# SCH_UNLOCK.net
KiCad netlist of a schematic drawn in Altium Designer
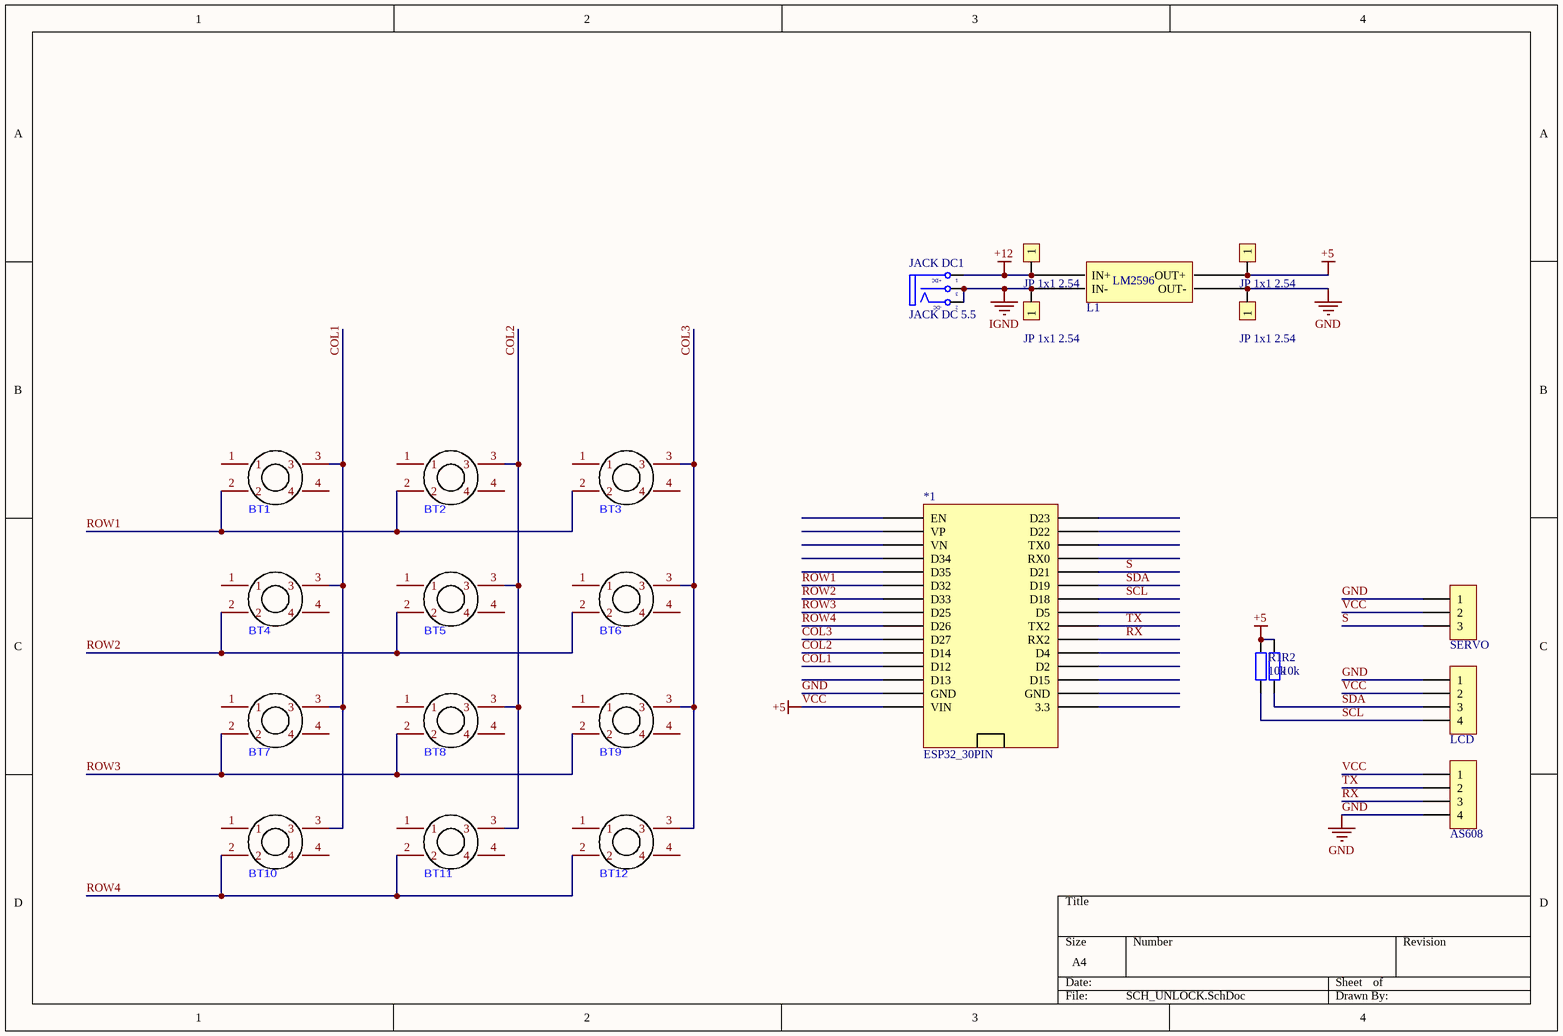
[diagram p0: SCH_UNLOCK.SchDoc]

(export (version "E")
  (design (tool "Eeschema 10.0.6"))
  (components
    (comp (ref "*1")
      (value "ESP32_30PIN")
      (footprint "ESP32_30PIN")
      (libsource (lib "myAltium") (part "ESP32_30PIN"))
    )
    (comp (ref "BT1")
      (value "Nut Nhan 4 chan 12x12")
      (footprint "12X12 BUTTOM Blue")
      (libsource (lib "Altium_Lib_by_KhueNguyenCreator") (part "Nut Nhan 4 chan 12x12"))
    )
    (comp (ref "BT2")
      (value "Nut Nhan 4 chan 12x12")
      (footprint "12X12 BUTTOM Blue")
      (libsource (lib "Altium_Lib_by_KhueNguyenCreator") (part "Nut Nhan 4 chan 12x12"))
    )
    (comp (ref "BT3")
      (value "Nut Nhan 4 chan 12x12")
      (footprint "12X12 BUTTOM Blue")
      (libsource (lib "Altium_Lib_by_KhueNguyenCreator") (part "Nut Nhan 4 chan 12x12"))
    )
    (comp (ref "BT4")
      (value "Nut Nhan 4 chan 12x12")
      (footprint "12X12 BUTTOM Blue")
      (libsource (lib "Altium_Lib_by_KhueNguyenCreator") (part "Nut Nhan 4 chan 12x12"))
    )
    (comp (ref "BT5")
      (value "Nut Nhan 4 chan 12x12")
      (footprint "12X12 BUTTOM Blue")
      (libsource (lib "Altium_Lib_by_KhueNguyenCreator") (part "Nut Nhan 4 chan 12x12"))
    )
    (comp (ref "BT6")
      (value "Nut Nhan 4 chan 12x12")
      (footprint "12X12 BUTTOM Blue")
      (libsource (lib "Altium_Lib_by_KhueNguyenCreator") (part "Nut Nhan 4 chan 12x12"))
    )
    (comp (ref "BT7")
      (value "Nut Nhan 4 chan 12x12")
      (footprint "12X12 BUTTOM Blue")
      (libsource (lib "Altium_Lib_by_KhueNguyenCreator") (part "Nut Nhan 4 chan 12x12"))
    )
    (comp (ref "BT8")
      (value "Nut Nhan 4 chan 12x12")
      (footprint "12X12 BUTTOM Blue")
      (libsource (lib "Altium_Lib_by_KhueNguyenCreator") (part "Nut Nhan 4 chan 12x12"))
    )
    (comp (ref "BT9")
      (value "Nut Nhan 4 chan 12x12")
      (footprint "12X12 BUTTOM Blue")
      (libsource (lib "Altium_Lib_by_KhueNguyenCreator") (part "Nut Nhan 4 chan 12x12"))
    )
    (comp (ref "BT10")
      (value "Nut Nhan 4 chan 12x12")
      (footprint "12X12 BUTTOM Blue")
      (libsource (lib "Altium_Lib_by_KhueNguyenCreator") (part "Nut Nhan 4 chan 12x12"))
    )
    (comp (ref "BT11")
      (value "Nut Nhan 4 chan 12x12")
      (footprint "12X12 BUTTOM Blue")
      (libsource (lib "Altium_Lib_by_KhueNguyenCreator") (part "Nut Nhan 4 chan 12x12"))
    )
    (comp (ref "BT12")
      (value "Nut Nhan 4 chan 12x12")
      (footprint "12X12 BUTTOM Blue")
      (libsource (lib "Altium_Lib_by_KhueNguyenCreator") (part "Nut Nhan 4 chan 12x12"))
    )
    (comp (ref "H1")
      (value "SERVO")
      (footprint "XH2.54M-3")
      (description "Cắm")
      (libsource (lib "Altium_Lib_by_KhueNguyenCreator") (part "Header 3P 2.54 Duc Thang"))
    )
    (comp (ref "H2")
      (value "LCD")
      (footprint "XH2.54M-4")
      (description "Cắm")
      (libsource (lib "Altium_Lib_by_KhueNguyenCreator") (part "Header 4P 2.54 Duc Thang"))
    )
    (comp (ref "H3")
      (value "AS608")
      (footprint "XH2.54M-4")
      (description "Cắm")
      (libsource (lib "Altium_Lib_by_KhueNguyenCreator") (part "Header 4P 2.54 Duc Thang"))
    )
    (comp (ref "JACK DC1")
      (value "JACK DC 5.5")
      (footprint "JACK DC 5.5")
      (libsource (lib "Altium_Lib_by_KhueNguyenCreator") (part "JACK DC 5.5"))
    )
    (comp (ref "JP1")
      (value "JP 1x1 2.54")
      (footprint "JP 1x1 DT")
      (description "Cắm")
      (libsource (lib "") (part "JP 1x1 2.54 Duc Cong_1"))
    )
    (comp (ref "JP2")
      (value "JP 1x1 2.54")
      (footprint "JP 1x1 DT")
      (description "Cắm")
      (libsource (lib "") (part "JP 1x1 2.54 Duc Cong_1"))
    )
    (comp (ref "JP3")
      (value "JP 1x1 2.54")
      (footprint "JP 1x1 DT")
      (description "Cắm")
      (libsource (lib "Altium_Lib_by_KhueNguyenCreator") (part "JP 1x1 2.54 Duc Cong"))
    )
    (comp (ref "JP4")
      (value "JP 1x1 2.54")
      (footprint "JP 1x1 DT")
      (description "Cắm")
      (libsource (lib "Altium_Lib_by_KhueNguyenCreator") (part "JP 1x1 2.54 Duc Cong"))
    )
    (comp (ref "L1")
      (value "BUCK_LM2596")
      (footprint "BUCK_LM2596")
      (libsource (lib "BUCK_LM2596_Library") (part "BUCK_LM2596"))
    )
    (comp (ref "R1")
      (value "10k")
      (footprint "tro vach 1/4w")
      (description "Căm")
      (libsource (lib "Altium_Lib_by_KhueNguyenCreator") (part "Tro Vach 1/4W 5% 10k"))
    )
    (comp (ref "R2")
      (value "10k")
      (footprint "tro vach 1/4w")
      (description "Căm")
      (libsource (lib "Altium_Lib_by_KhueNguyenCreator") (part "Tro Vach 1/4W 5% 10k"))
    )
  )
  (nets
    (net (code "1") (name "+5") (class "Default")
      (node (ref "*1") (pin "VIN") (pinfunction "VIN_VIN") (pintype "passive"))
      (node (ref "H1") (pin "2") (pinfunction "2_2") (pintype "passive"))
      (node (ref "H2") (pin "2") (pinfunction "2_2") (pintype "passive"))
      (node (ref "H3") (pin "1") (pinfunction "1_1") (pintype "passive"))
      (node (ref "JP2") (pin "1") (pinfunction "1_1") (pintype "passive"))
      (node (ref "L1") (pin "4") (pinfunction "OUT+_4") (pintype "passive"))
      (node (ref "R1") (pin "1") (pinfunction "1_1") (pintype "passive"))
      (node (ref "R2") (pin "1") (pinfunction "1_1") (pintype "passive"))
    )
    (net (code "2") (name "+12") (class "Default")
      (node (ref "JACK DC1") (pin "1") (pinfunction "T_1") (pintype "passive"))
      (node (ref "JP1") (pin "1") (pinfunction "1_1") (pintype "passive"))
      (node (ref "L1") (pin "1") (pinfunction "IN+_1") (pintype "passive"))
    )
    (net (code "3") (name "/COL1") (class "Default")
      (node (ref "*1") (pin "D12") (pinfunction "D12_D12") (pintype "passive"))
      (node (ref "BT1") (pin "3") (pinfunction "3_3") (pintype "passive"))
      (node (ref "BT10") (pin "3") (pinfunction "3_3") (pintype "passive"))
      (node (ref "BT4") (pin "3") (pinfunction "3_3") (pintype "passive"))
      (node (ref "BT7") (pin "3") (pinfunction "3_3") (pintype "passive"))
    )
    (net (code "4") (name "/COL2") (class "Default")
      (node (ref "*1") (pin "D14") (pinfunction "D14_D14") (pintype "passive"))
      (node (ref "BT11") (pin "3") (pinfunction "3_3") (pintype "passive"))
      (node (ref "BT2") (pin "3") (pinfunction "3_3") (pintype "passive"))
      (node (ref "BT5") (pin "3") (pinfunction "3_3") (pintype "passive"))
      (node (ref "BT8") (pin "3") (pinfunction "3_3") (pintype "passive"))
    )
    (net (code "5") (name "/COL3") (class "Default")
      (node (ref "*1") (pin "D27") (pinfunction "D27_D27") (pintype "passive"))
      (node (ref "BT12") (pin "3") (pinfunction "3_3") (pintype "passive"))
      (node (ref "BT3") (pin "3") (pinfunction "3_3") (pintype "passive"))
      (node (ref "BT6") (pin "3") (pinfunction "3_3") (pintype "passive"))
      (node (ref "BT9") (pin "3") (pinfunction "3_3") (pintype "passive"))
    )
    (net (code "6") (name "/ROW1") (class "Default")
      (node (ref "*1") (pin "D32") (pinfunction "D32_D32") (pintype "passive"))
      (node (ref "BT1") (pin "2") (pinfunction "2_2") (pintype "passive"))
      (node (ref "BT2") (pin "2") (pinfunction "2_2") (pintype "passive"))
      (node (ref "BT3") (pin "2") (pinfunction "2_2") (pintype "passive"))
    )
    (net (code "7") (name "/ROW2") (class "Default")
      (node (ref "*1") (pin "D33") (pinfunction "D33_D33") (pintype "passive"))
      (node (ref "BT4") (pin "2") (pinfunction "2_2") (pintype "passive"))
      (node (ref "BT5") (pin "2") (pinfunction "2_2") (pintype "passive"))
      (node (ref "BT6") (pin "2") (pinfunction "2_2") (pintype "passive"))
    )
    (net (code "8") (name "/ROW3") (class "Default")
      (node (ref "*1") (pin "D25") (pinfunction "D25_D25") (pintype "passive"))
      (node (ref "BT7") (pin "2") (pinfunction "2_2") (pintype "passive"))
      (node (ref "BT8") (pin "2") (pinfunction "2_2") (pintype "passive"))
      (node (ref "BT9") (pin "2") (pinfunction "2_2") (pintype "passive"))
    )
    (net (code "9") (name "/ROW4") (class "Default")
      (node (ref "*1") (pin "D26") (pinfunction "D26_D26") (pintype "passive"))
      (node (ref "BT10") (pin "2") (pinfunction "2_2") (pintype "passive"))
      (node (ref "BT11") (pin "2") (pinfunction "2_2") (pintype "passive"))
      (node (ref "BT12") (pin "2") (pinfunction "2_2") (pintype "passive"))
    )
    (net (code "10") (name "/RX") (class "Default")
      (node (ref "*1") (pin "RX2") (pinfunction "RX2_RX2") (pintype "passive"))
      (node (ref "H3") (pin "3") (pinfunction "3_3") (pintype "passive"))
    )
    (net (code "11") (name "/S") (class "Default")
      (node (ref "*1") (pin "D21") (pinfunction "D21_D21") (pintype "passive"))
      (node (ref "H1") (pin "3") (pinfunction "3_3") (pintype "passive"))
    )
    (net (code "12") (name "/SCL") (class "Default")
      (node (ref "*1") (pin "D18") (pinfunction "D18_D18") (pintype "passive"))
      (node (ref "H2") (pin "4") (pinfunction "4_4") (pintype "passive"))
      (node (ref "R1") (pin "2") (pinfunction "2_2") (pintype "passive"))
    )
    (net (code "13") (name "/SDA") (class "Default")
      (node (ref "*1") (pin "D19") (pinfunction "D19_D19") (pintype "passive"))
      (node (ref "H2") (pin "3") (pinfunction "3_3") (pintype "passive"))
      (node (ref "R2") (pin "2") (pinfunction "2_2") (pintype "passive"))
    )
    (net (code "14") (name "/TX") (class "Default")
      (node (ref "*1") (pin "TX2") (pinfunction "TX2_TX2") (pintype "passive"))
      (node (ref "H3") (pin "2") (pinfunction "2_2") (pintype "passive"))
    )
    (net (code "15") (name "GND") (class "Default")
      (node (ref "*1") (pin "GND") (pinfunction "GND_GND") (pintype "passive"))
      (node (ref "H1") (pin "1") (pinfunction "1_1") (pintype "passive"))
      (node (ref "H2") (pin "1") (pinfunction "1_1") (pintype "passive"))
      (node (ref "H3") (pin "4") (pinfunction "4_4") (pintype "passive"))
      (node (ref "JP4") (pin "1") (pinfunction "1_1") (pintype "passive"))
      (node (ref "L1") (pin "3") (pinfunction "OUT-_3") (pintype "passive"))
    )
    (net (code "16") (name "IGND") (class "Default")
      (node (ref "JACK DC1") (pin "2") (pinfunction "TN_2") (pintype "passive"))
      (node (ref "JACK DC1") (pin "3") (pinfunction "S_3") (pintype "power_in"))
      (node (ref "JP3") (pin "1") (pinfunction "1_1") (pintype "passive"))
      (node (ref "L1") (pin "2") (pinfunction "IN-_2") (pintype "passive"))
    )
    (net (code "17") (name "unconnected-(*1-Pad3.3)") (class "Default")
      (node (ref "*1") (pin "3.3") (pinfunction "3.3_3.3") (pintype "passive"))
    )
    (net (code "18") (name "unconnected-(*1-PadD2)") (class "Default")
      (node (ref "*1") (pin "D2") (pinfunction "D2_D2") (pintype "passive"))
    )
    (net (code "19") (name "unconnected-(*1-PadD4)") (class "Default")
      (node (ref "*1") (pin "D4") (pinfunction "D4_D4") (pintype "passive"))
    )
    (net (code "20") (name "unconnected-(*1-PadD5)") (class "Default")
      (node (ref "*1") (pin "D5") (pinfunction "D5_D5") (pintype "passive"))
    )
    (net (code "21") (name "unconnected-(*1-PadD13)") (class "Default")
      (node (ref "*1") (pin "D13") (pinfunction "D13_D13") (pintype "passive"))
    )
    (net (code "22") (name "unconnected-(*1-PadD15)") (class "Default")
      (node (ref "*1") (pin "D15") (pinfunction "D15_D15") (pintype "passive"))
    )
    (net (code "23") (name "unconnected-(*1-PadD22)") (class "Default")
      (node (ref "*1") (pin "D22") (pinfunction "D22_D22") (pintype "passive"))
    )
    (net (code "24") (name "unconnected-(*1-PadD23)") (class "Default")
      (node (ref "*1") (pin "D23") (pinfunction "D23_D23") (pintype "passive"))
    )
    (net (code "25") (name "unconnected-(*1-PadD34)") (class "Default")
      (node (ref "*1") (pin "D34") (pinfunction "D34_D34") (pintype "passive"))
    )
    (net (code "26") (name "unconnected-(*1-PadD35)") (class "Default")
      (node (ref "*1") (pin "D35") (pinfunction "D35_D35") (pintype "passive"))
    )
    (net (code "27") (name "unconnected-(*1-PadEN)") (class "Default")
      (node (ref "*1") (pin "EN") (pinfunction "EN_EN") (pintype "passive"))
    )
    (net (code "28") (name "unconnected-(*1-PadGND)") (class "Default")
      (node (ref "*1") (pin "GND") (pinfunction "GND_GND") (pintype "passive"))
    )
    (net (code "29") (name "unconnected-(*1-PadRX0)") (class "Default")
      (node (ref "*1") (pin "RX0") (pinfunction "RX0_RX0") (pintype "passive"))
    )
    (net (code "30") (name "unconnected-(*1-PadTX0)") (class "Default")
      (node (ref "*1") (pin "TX0") (pinfunction "TX0_TX0") (pintype "passive"))
    )
    (net (code "31") (name "unconnected-(*1-PadVN)") (class "Default")
      (node (ref "*1") (pin "VN") (pinfunction "VN_VN") (pintype "passive"))
    )
    (net (code "32") (name "unconnected-(*1-PadVP)") (class "Default")
      (node (ref "*1") (pin "VP") (pinfunction "VP_VP") (pintype "passive"))
    )
    (net (code "33") (name "unconnected-(BT1-Pad1)") (class "Default")
      (node (ref "BT1") (pin "1") (pinfunction "1_1") (pintype "passive"))
    )
    (net (code "34") (name "unconnected-(BT1-Pad4)") (class "Default")
      (node (ref "BT1") (pin "4") (pinfunction "4_4") (pintype "passive"))
    )
    (net (code "35") (name "unconnected-(BT2-Pad1)") (class "Default")
      (node (ref "BT2") (pin "1") (pinfunction "1_1") (pintype "passive"))
    )
    (net (code "36") (name "unconnected-(BT2-Pad4)") (class "Default")
      (node (ref "BT2") (pin "4") (pinfunction "4_4") (pintype "passive"))
    )
    (net (code "37") (name "unconnected-(BT3-Pad1)") (class "Default")
      (node (ref "BT3") (pin "1") (pinfunction "1_1") (pintype "passive"))
    )
    (net (code "38") (name "unconnected-(BT3-Pad4)") (class "Default")
      (node (ref "BT3") (pin "4") (pinfunction "4_4") (pintype "passive"))
    )
    (net (code "39") (name "unconnected-(BT4-Pad1)") (class "Default")
      (node (ref "BT4") (pin "1") (pinfunction "1_1") (pintype "passive"))
    )
    (net (code "40") (name "unconnected-(BT4-Pad4)") (class "Default")
      (node (ref "BT4") (pin "4") (pinfunction "4_4") (pintype "passive"))
    )
    (net (code "41") (name "unconnected-(BT5-Pad1)") (class "Default")
      (node (ref "BT5") (pin "1") (pinfunction "1_1") (pintype "passive"))
    )
    (net (code "42") (name "unconnected-(BT5-Pad4)") (class "Default")
      (node (ref "BT5") (pin "4") (pinfunction "4_4") (pintype "passive"))
    )
    (net (code "43") (name "unconnected-(BT6-Pad1)") (class "Default")
      (node (ref "BT6") (pin "1") (pinfunction "1_1") (pintype "passive"))
    )
    (net (code "44") (name "unconnected-(BT6-Pad4)") (class "Default")
      (node (ref "BT6") (pin "4") (pinfunction "4_4") (pintype "passive"))
    )
    (net (code "45") (name "unconnected-(BT7-Pad1)") (class "Default")
      (node (ref "BT7") (pin "1") (pinfunction "1_1") (pintype "passive"))
    )
    (net (code "46") (name "unconnected-(BT7-Pad4)") (class "Default")
      (node (ref "BT7") (pin "4") (pinfunction "4_4") (pintype "passive"))
    )
    (net (code "47") (name "unconnected-(BT8-Pad1)") (class "Default")
      (node (ref "BT8") (pin "1") (pinfunction "1_1") (pintype "passive"))
    )
    (net (code "48") (name "unconnected-(BT8-Pad4)") (class "Default")
      (node (ref "BT8") (pin "4") (pinfunction "4_4") (pintype "passive"))
    )
    (net (code "49") (name "unconnected-(BT9-Pad1)") (class "Default")
      (node (ref "BT9") (pin "1") (pinfunction "1_1") (pintype "passive"))
    )
    (net (code "50") (name "unconnected-(BT9-Pad4)") (class "Default")
      (node (ref "BT9") (pin "4") (pinfunction "4_4") (pintype "passive"))
    )
    (net (code "51") (name "unconnected-(BT10-Pad1)") (class "Default")
      (node (ref "BT10") (pin "1") (pinfunction "1_1") (pintype "passive"))
    )
    (net (code "52") (name "unconnected-(BT10-Pad4)") (class "Default")
      (node (ref "BT10") (pin "4") (pinfunction "4_4") (pintype "passive"))
    )
    (net (code "53") (name "unconnected-(BT11-Pad1)") (class "Default")
      (node (ref "BT11") (pin "1") (pinfunction "1_1") (pintype "passive"))
    )
    (net (code "54") (name "unconnected-(BT11-Pad4)") (class "Default")
      (node (ref "BT11") (pin "4") (pinfunction "4_4") (pintype "passive"))
    )
    (net (code "55") (name "unconnected-(BT12-Pad1)") (class "Default")
      (node (ref "BT12") (pin "1") (pinfunction "1_1") (pintype "passive"))
    )
    (net (code "56") (name "unconnected-(BT12-Pad4)") (class "Default")
      (node (ref "BT12") (pin "4") (pinfunction "4_4") (pintype "passive"))
    )
  )
)
